# 4_EXT_USR_LED.net
KiCad netlist of a schematic drawn in Altium Designer
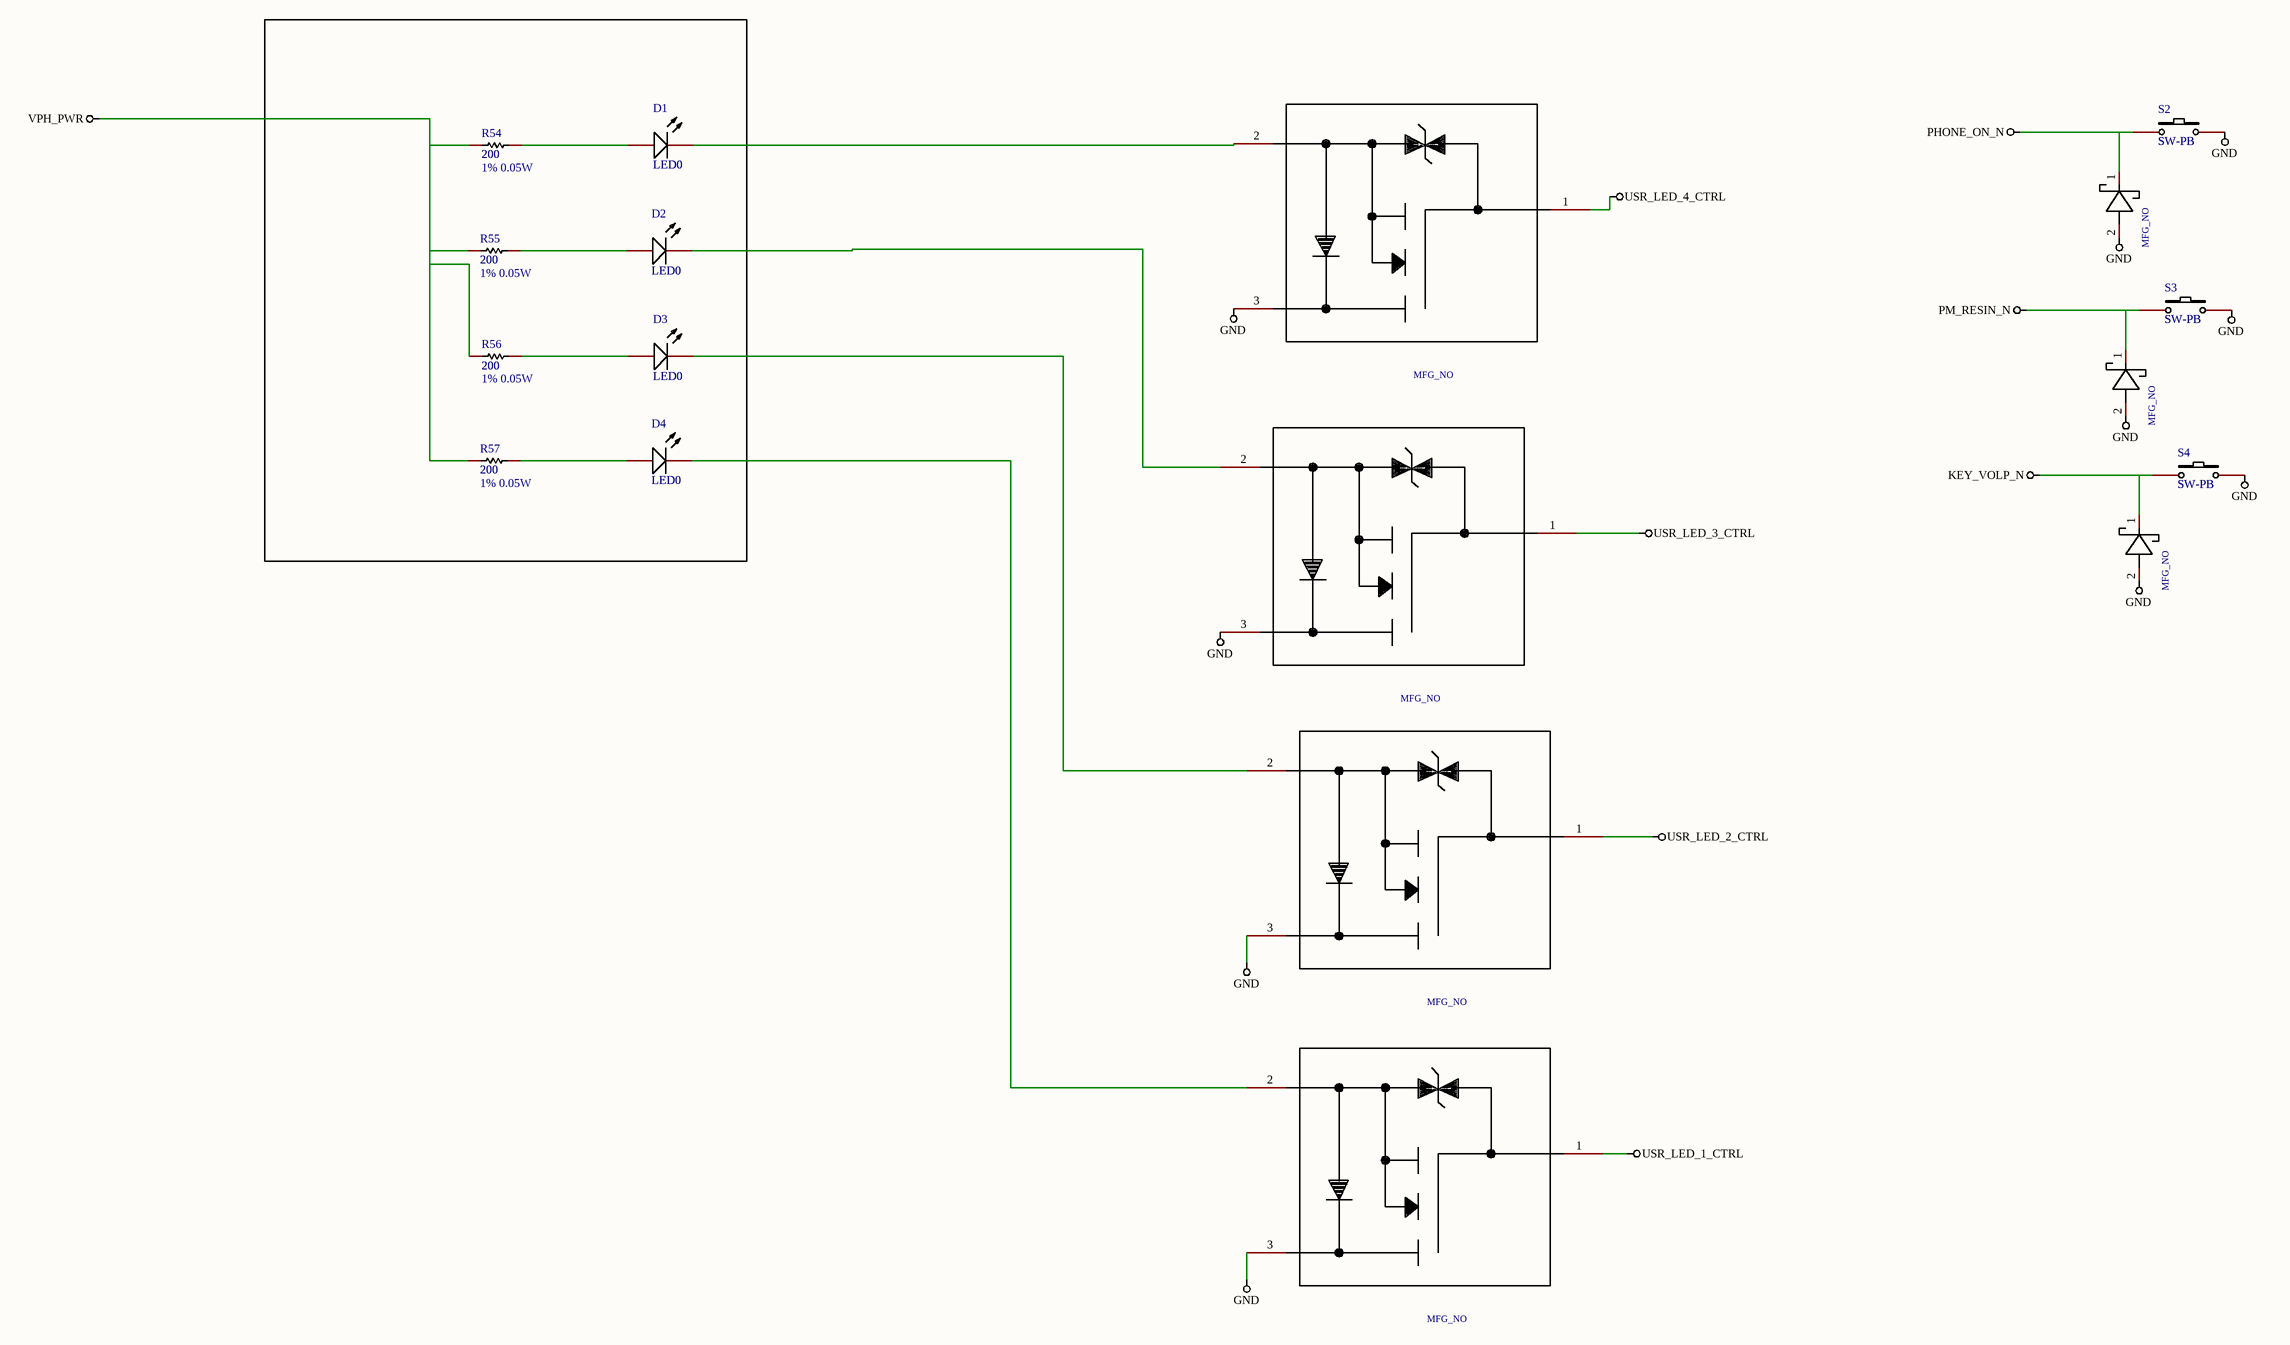
[diagram p0: 4_EXT_USR_LED.schdoc]

(export (version "E")
  (design (tool "Eeschema 10.0.6"))
  (components
    (comp (ref "CR0")
      (value "SCHOTTKY")
      (fields
        (field (name "PART_NUMBER") "MCN_NO")
        (field (name "PART_ID") "MFG_NO")
        (field (name "LIBRARY NAME") "MSM8916_DRAM_PMIC_REF_Library")
      )
      (libsource (lib "altium-import") (part "root_1_SCHOTTKY_"))
    )
    (comp (ref "CR1")
      (value "SCHOTTKY")
      (fields
        (field (name "PART_NUMBER") "MCN_NO")
        (field (name "PART_ID") "MFG_NO")
        (field (name "LIBRARY NAME") "MSM8916_DRAM_PMIC_REF_Library")
      )
      (libsource (lib "altium-import") (part "root_1_SCHOTTKY_"))
    )
    (comp (ref "CR2")
      (value "SCHOTTKY")
      (fields
        (field (name "PART_NUMBER") "MCN_NO")
        (field (name "PART_ID") "MFG_NO")
        (field (name "LIBRARY NAME") "MSM8916_DRAM_PMIC_REF_Library")
      )
      (libsource (lib "altium-import") (part "root_1_SCHOTTKY_"))
    )
    (comp (ref "D1")
      (value "LED0")
      (description "Typical INFRARED GaAs LED")
      (fields (field (name "NAME") "LED0") (field (name "PUBLISHER") "Altium Limited"))
      (libsource (lib "altium-import") (part "root_0_LED0_"))
    )
    (comp (ref "D2")
      (value "LED0")
      (description "Typical INFRARED GaAs LED")
      (fields (field (name "NAME") "LED0") (field (name "PUBLISHER") "Altium Limited"))
      (libsource (lib "altium-import") (part "root_0_LED0_"))
    )
    (comp (ref "D3")
      (value "LED0")
      (description "Typical INFRARED GaAs LED")
      (fields (field (name "NAME") "LED0") (field (name "PUBLISHER") "Altium Limited"))
      (libsource (lib "altium-import") (part "root_0_LED0_"))
    )
    (comp (ref "D4")
      (value "LED0")
      (description "Typical INFRARED GaAs LED")
      (fields (field (name "NAME") "LED0") (field (name "PUBLISHER") "Altium Limited"))
      (libsource (lib "altium-import") (part "root_0_LED0_"))
    )
    (comp (ref "Q2")
      (value "nfet_zener_bidir")
      (fields
        (field (name "PART_NUMBER") "MCN_NO")
        (field (name "PART_ID") "MFG_NO")
        (field (name "LIBRARY NAME") "MSM8916_DRAM_PMIC_REF_Library")
      )
      (libsource (lib "altium-import") (part "root_2_nfet_zener_bidir_"))
    )
    (comp (ref "Q3")
      (value "nfet_zener_bidir")
      (fields
        (field (name "PART_NUMBER") "MCN_NO")
        (field (name "PART_ID") "MFG_NO")
        (field (name "LIBRARY NAME") "MSM8916_DRAM_PMIC_REF_Library")
      )
      (libsource (lib "altium-import") (part "root_2_nfet_zener_bidir_"))
    )
    (comp (ref "Q4")
      (value "nfet_zener_bidir")
      (fields
        (field (name "PART_NUMBER") "MCN_NO")
        (field (name "PART_ID") "MFG_NO")
        (field (name "LIBRARY NAME") "MSM8916_DRAM_PMIC_REF_Library")
      )
      (libsource (lib "altium-import") (part "root_2_nfet_zener_bidir_"))
    )
    (comp (ref "Q5")
      (value "nfet_zener_bidir")
      (fields
        (field (name "PART_NUMBER") "MCN_NO")
        (field (name "PART_ID") "MFG_NO")
        (field (name "LIBRARY NAME") "MSM8916_DRAM_PMIC_REF_Library")
      )
      (libsource (lib "altium-import") (part "root_2_nfet_zener_bidir_"))
    )
    (comp (ref "R54")
      (value "200")
      (description "Resistor")
      (fields
        (field (name "NAME") "200")
        (field (name "ALTIUM_VALUE") "1% 0.05W")
        (field (name "PUBLISHER") "Altium Limited")
      )
      (libsource (lib "altium-import") (part "root_0_200_"))
    )
    (comp (ref "R55")
      (value "200")
      (description "Resistor")
      (fields
        (field (name "NAME") "200")
        (field (name "ALTIUM_VALUE") "1% 0.05W")
        (field (name "PUBLISHER") "Altium Limited")
      )
      (libsource (lib "altium-import") (part "root_0_200_"))
    )
    (comp (ref "R56")
      (value "200")
      (description "Resistor")
      (fields
        (field (name "NAME") "200")
        (field (name "ALTIUM_VALUE") "1% 0.05W")
        (field (name "PUBLISHER") "Altium Limited")
      )
      (libsource (lib "altium-import") (part "root_0_200_"))
    )
    (comp (ref "R57")
      (value "200")
      (description "Resistor")
      (fields
        (field (name "NAME") "200")
        (field (name "ALTIUM_VALUE") "1% 0.05W")
        (field (name "PUBLISHER") "Altium Limited")
      )
      (libsource (lib "altium-import") (part "root_0_200_"))
    )
    (comp (ref "S2")
      (value "SW-PB")
      (description "Switch")
      (fields (field (name "NAME") "SW-PB") (field (name "PUBLISHER") "Altium Limited"))
      (libsource (lib "altium-import") (part "root_0_SW-PB_"))
    )
    (comp (ref "S3")
      (value "SW-PB")
      (description "Switch")
      (fields (field (name "NAME") "SW-PB") (field (name "PUBLISHER") "Altium Limited"))
      (libsource (lib "altium-import") (part "root_0_SW-PB_"))
    )
    (comp (ref "S4")
      (value "SW-PB")
      (description "Switch")
      (fields (field (name "NAME") "SW-PB") (field (name "PUBLISHER") "Altium Limited"))
      (libsource (lib "altium-import") (part "root_0_SW-PB_"))
    )
  )
  (nets
    (net (code "1") (name "GND") (class "Default")
      (node (ref "CR0") (pin "2") (pinfunction "POS_2") (pintype "passive"))
      (node (ref "CR1") (pin "2") (pinfunction "POS_2") (pintype "passive"))
      (node (ref "CR2") (pin "2") (pinfunction "POS_2") (pintype "passive"))
      (node (ref "Q2") (pin "3") (pinfunction "D_3") (pintype "passive"))
      (node (ref "Q3") (pin "3") (pinfunction "D_3") (pintype "passive"))
      (node (ref "Q4") (pin "3") (pinfunction "D_3") (pintype "passive"))
      (node (ref "Q5") (pin "3") (pinfunction "D_3") (pintype "passive"))
      (node (ref "S2") (pin "2") (pinfunction "2_2") (pintype "passive"))
      (node (ref "S3") (pin "2") (pinfunction "2_2") (pintype "passive"))
      (node (ref "S4") (pin "2") (pinfunction "2_2") (pintype "passive"))
    )
    (net (code "2") (name "KEY_VOLP_N") (class "Default")
      (node (ref "CR2") (pin "1") (pinfunction "NEG_1") (pintype "passive"))
      (node (ref "S4") (pin "1") (pinfunction "1_1") (pintype "passive"))
    )
    (net (code "3") (name "Net-(D1-A)") (class "Default")
      (node (ref "D1") (pin "1") (pinfunction "A_1") (pintype "passive"))
      (node (ref "R54") (pin "2") (pinfunction "2_2") (pintype "passive"))
    )
    (net (code "4") (name "Net-(D1-K)") (class "Default")
      (node (ref "D1") (pin "2") (pinfunction "K_2") (pintype "passive"))
      (node (ref "Q2") (pin "2") (pinfunction "S_2") (pintype "passive"))
    )
    (net (code "5") (name "Net-(D2-A)") (class "Default")
      (node (ref "D2") (pin "1") (pinfunction "A_1") (pintype "passive"))
      (node (ref "R55") (pin "2") (pinfunction "2_2") (pintype "passive"))
    )
    (net (code "6") (name "Net-(D2-K)") (class "Default")
      (node (ref "D2") (pin "2") (pinfunction "K_2") (pintype "passive"))
      (node (ref "Q3") (pin "2") (pinfunction "S_2") (pintype "passive"))
    )
    (net (code "7") (name "Net-(D3-A)") (class "Default")
      (node (ref "D3") (pin "1") (pinfunction "A_1") (pintype "passive"))
      (node (ref "R56") (pin "2") (pinfunction "2_2") (pintype "passive"))
    )
    (net (code "8") (name "Net-(D3-K)") (class "Default")
      (node (ref "D3") (pin "2") (pinfunction "K_2") (pintype "passive"))
      (node (ref "Q4") (pin "2") (pinfunction "S_2") (pintype "passive"))
    )
    (net (code "9") (name "Net-(D4-A)") (class "Default")
      (node (ref "D4") (pin "1") (pinfunction "A_1") (pintype "passive"))
      (node (ref "R57") (pin "2") (pinfunction "2_2") (pintype "passive"))
    )
    (net (code "10") (name "Net-(D4-K)") (class "Default")
      (node (ref "D4") (pin "2") (pinfunction "K_2") (pintype "passive"))
      (node (ref "Q5") (pin "2") (pinfunction "S_2") (pintype "passive"))
    )
    (net (code "11") (name "PHONE_ON_N") (class "Default")
      (node (ref "CR0") (pin "1") (pinfunction "NEG_1") (pintype "passive"))
      (node (ref "S2") (pin "1") (pinfunction "1_1") (pintype "passive"))
    )
    (net (code "12") (name "PM_RESIN_N") (class "Default")
      (node (ref "CR1") (pin "1") (pinfunction "NEG_1") (pintype "passive"))
      (node (ref "S3") (pin "1") (pinfunction "1_1") (pintype "passive"))
    )
    (net (code "13") (name "USR_LED_1_CTRL") (class "Default")
      (node (ref "Q5") (pin "1") (pinfunction "G_1") (pintype "passive"))
    )
    (net (code "14") (name "USR_LED_2_CTRL") (class "Default")
      (node (ref "Q4") (pin "1") (pinfunction "G_1") (pintype "passive"))
    )
    (net (code "15") (name "USR_LED_3_CTRL") (class "Default")
      (node (ref "Q3") (pin "1") (pinfunction "G_1") (pintype "passive"))
    )
    (net (code "16") (name "USR_LED_4_CTRL") (class "Default")
      (node (ref "Q2") (pin "1") (pinfunction "G_1") (pintype "passive"))
    )
    (net (code "17") (name "VPH_PWR") (class "Default")
      (node (ref "R54") (pin "1") (pinfunction "1_1") (pintype "passive"))
      (node (ref "R55") (pin "1") (pinfunction "1_1") (pintype "passive"))
      (node (ref "R56") (pin "1") (pinfunction "1_1") (pintype "passive"))
      (node (ref "R57") (pin "1") (pinfunction "1_1") (pintype "passive"))
    )
  )
)
